# AB_-_Eagle.net
KiCad netlist of a schematic drawn in EAGLE
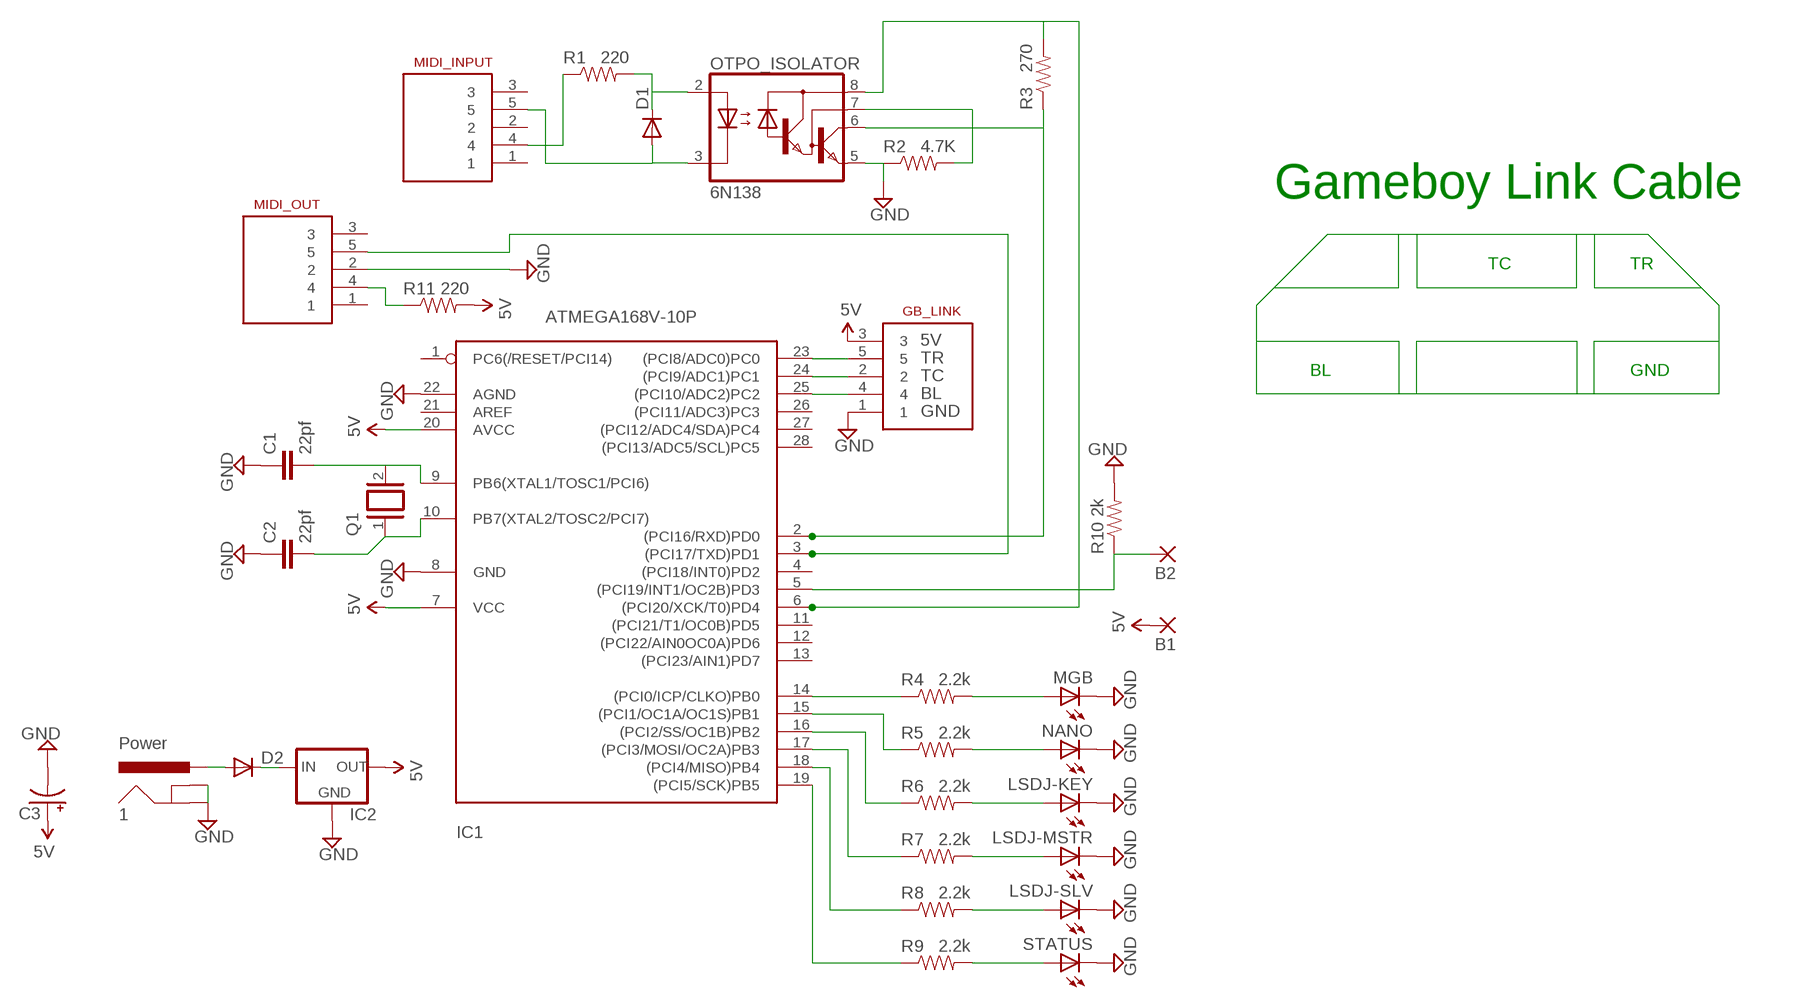
[diagram p0: schematic, sheet 1]

(export (version "E")
  (design (tool "Eeschema 10.0.6"))
  (components
    (comp (ref "1")
      (value "Power")
      (footprint "eagle-import:POWER_JACK_PTH")
      (libsource (lib "eagle-import") (part "POWER_JACKPTH"))
    )
    (comp (ref "B1")
      (value "2,15/1,0")
      (footprint "eagle-import:2,15_1,0")
      (libsource (lib "eagle-import") (part "2,15/1,0"))
    )
    (comp (ref "B2")
      (value "2,15/1,0")
      (footprint "eagle-import:2,15_1,0")
      (libsource (lib "eagle-import") (part "2,15/1,0"))
    )
    (comp (ref "C1")
      (value "22pf")
      (footprint "eagle-import:CAP-PTH-SMALL2")
      (libsource (lib "eagle-import") (part "CAPPTH2"))
    )
    (comp (ref "C2")
      (value "22pf")
      (footprint "eagle-import:CAP-PTH-SMALL2")
      (libsource (lib "eagle-import") (part "CAPPTH2"))
    )
    (comp (ref "C3")
      (value "CAP_POLPTH2")
      (footprint "eagle-import:CPOL-RADIAL-10UF-25V")
      (libsource (lib "eagle-import") (part "CAP_POLPTH2"))
    )
    (comp (ref "D1")
      (value "DIODE1N4148")
      (footprint "eagle-import:DIODE-1N4148")
      (libsource (lib "eagle-import") (part "DIODE1N4148"))
    )
    (comp (ref "D2")
      (value "DIODE1N4148")
      (footprint "eagle-import:DIODE-1N4148")
      (libsource (lib "eagle-import") (part "DIODE1N4148"))
    )
    (comp (ref "GB_LINK")
      (value "MIDI_CONN_FEMALE_SUPPORT")
      (footprint "eagle-import:DIN_5_FEMALE_SUPPORT")
      (libsource (lib "eagle-import") (part "MIDI_CONN_FEMALE_SUPPORT"))
    )
    (comp (ref "IC1")
      (value "ATMEGA168V-10P")
      (footprint "eagle-import:DIL28-3")
      (libsource (lib "eagle-import") (part "ATMEGA168PV-10"))
    )
    (comp (ref "IC2")
      (value "V_REG_78XX-TO-220")
      (footprint "eagle-import:TO-220-ALT")
      (libsource (lib "eagle-import") (part "V_REG_78XX-TO-220"))
    )
    (comp (ref "LSDJ-KEY")
      (value "LED3MM")
      (footprint "eagle-import:LED3MM")
      (libsource (lib "eagle-import") (part "LED3MM"))
    )
    (comp (ref "LSDJ-MSTR")
      (value "LED3MM")
      (footprint "eagle-import:LED3MM")
      (libsource (lib "eagle-import") (part "LED3MM"))
    )
    (comp (ref "LSDJ-SLV")
      (value "LED3MM")
      (footprint "eagle-import:LED3MM")
      (libsource (lib "eagle-import") (part "LED3MM"))
    )
    (comp (ref "MGB")
      (value "LED3MM")
      (footprint "eagle-import:LED3MM")
      (libsource (lib "eagle-import") (part "LED3MM"))
    )
    (comp (ref "MIDI_INPUT")
      (value "MIDI_CONN_FEMALE_SUPPORT")
      (footprint "eagle-import:DIN_5_FEMALE_SUPPORT")
      (libsource (lib "eagle-import") (part "MIDI_CONN_FEMALE_SUPPORT"))
    )
    (comp (ref "MIDI_OUT")
      (value "MIDI_CONN_FEMALE_SUPPORT")
      (footprint "eagle-import:DIN_5_FEMALE_SUPPORT")
      (libsource (lib "eagle-import") (part "MIDI_CONN_FEMALE_SUPPORT"))
    )
    (comp (ref "NANO")
      (value "LED3MM")
      (footprint "eagle-import:LED3MM")
      (libsource (lib "eagle-import") (part "LED3MM"))
    )
    (comp (ref "OTPO_ISOLATOR")
      (value "6N138")
      (footprint "eagle-import:DIL08")
      (fields (field (name "MF") "VISHAY/TELEFUNKEN"))
      (libsource (lib "eagle-import") (part "6N138"))
    )
    (comp (ref "Q1")
      (value "XTAL/S")
      (footprint "eagle-import:QS")
      (libsource (lib "eagle-import") (part "XTAL/S"))
    )
    (comp (ref "R1")
      (value "220")
      (footprint "eagle-import:AXIAL-0.3")
      (libsource (lib "eagle-import") (part "RESISTORAXIAL-0.3"))
    )
    (comp (ref "R2")
      (value "4.7K")
      (footprint "eagle-import:AXIAL-0.3")
      (libsource (lib "eagle-import") (part "RESISTORAXIAL-0.3"))
    )
    (comp (ref "R3")
      (value "270")
      (footprint "eagle-import:AXIAL-0.3")
      (libsource (lib "eagle-import") (part "RESISTORAXIAL-0.3"))
    )
    (comp (ref "R4")
      (value "2.2k")
      (footprint "eagle-import:AXIAL-0.3")
      (libsource (lib "eagle-import") (part "RESISTORAXIAL-0.3"))
    )
    (comp (ref "R5")
      (value "2.2k")
      (footprint "eagle-import:AXIAL-0.3")
      (libsource (lib "eagle-import") (part "RESISTORAXIAL-0.3"))
    )
    (comp (ref "R6")
      (value "2.2k")
      (footprint "eagle-import:AXIAL-0.3")
      (libsource (lib "eagle-import") (part "RESISTORAXIAL-0.3"))
    )
    (comp (ref "R7")
      (value "2.2k")
      (footprint "eagle-import:AXIAL-0.3")
      (libsource (lib "eagle-import") (part "RESISTORAXIAL-0.3"))
    )
    (comp (ref "R8")
      (value "2.2k")
      (footprint "eagle-import:AXIAL-0.3")
      (libsource (lib "eagle-import") (part "RESISTORAXIAL-0.3"))
    )
    (comp (ref "R9")
      (value "2.2k")
      (footprint "eagle-import:AXIAL-0.3")
      (libsource (lib "eagle-import") (part "RESISTORAXIAL-0.3"))
    )
    (comp (ref "R10")
      (value "2k")
      (footprint "eagle-import:AXIAL-0.3")
      (libsource (lib "eagle-import") (part "RESISTORAXIAL-0.3"))
    )
    (comp (ref "R11")
      (value "220")
      (footprint "eagle-import:AXIAL-0.3")
      (libsource (lib "eagle-import") (part "RESISTORAXIAL-0.3"))
    )
    (comp (ref "STATUS")
      (value "LED3MM")
      (footprint "eagle-import:LED3MM")
      (libsource (lib "eagle-import") (part "LED3MM"))
    )
  )
  (nets
    (net (code "1") (name "5V") (class "Default")
      (node (ref "B1") (pin "1") (pinfunction "P_1") (pintype "passive"))
      (node (ref "C3") (pin "1") (pinfunction "+_1") (pintype "passive"))
      (node (ref "GB_LINK") (pin "3") (pinfunction "3_3") (pintype "bidirectional"))
      (node (ref "IC1") (pin "20") (pinfunction "AVCC_20") (pintype "bidirectional"))
      (node (ref "IC1") (pin "7") (pinfunction "VCC_7") (pintype "bidirectional"))
      (node (ref "IC2") (pin "OUT") (pinfunction "OUT_OUT") (pintype "output"))
      (node (ref "R11") (pin "P$2") (pinfunction "2_P$2") (pintype "passive"))
    )
    (net (code "2") (name "GND") (class "Default")
      (node (ref "1") (pin "GND") (pinfunction "GND_GND") (pintype "bidirectional"))
      (node (ref "1") (pin "GNDBREAK") (pinfunction "GNDBREAK_GNDBREAK") (pintype "bidirectional"))
      (node (ref "C1") (pin "1") (pinfunction "1_1") (pintype "passive"))
      (node (ref "C2") (pin "1") (pinfunction "1_1") (pintype "passive"))
      (node (ref "C3") (pin "2") (pinfunction "-_2") (pintype "passive"))
      (node (ref "GB_LINK") (pin "1") (pinfunction "1_1") (pintype "bidirectional"))
      (node (ref "IC1") (pin "22") (pinfunction "AGND_22") (pintype "bidirectional"))
      (node (ref "IC1") (pin "8") (pinfunction "GND_8") (pintype "bidirectional"))
      (node (ref "IC2") (pin "GND") (pinfunction "GND_GND") (pintype "input"))
      (node (ref "LSDJ-KEY") (pin "K") (pinfunction "C_K") (pintype "passive"))
      (node (ref "LSDJ-MSTR") (pin "K") (pinfunction "C_K") (pintype "passive"))
      (node (ref "LSDJ-SLV") (pin "K") (pinfunction "C_K") (pintype "passive"))
      (node (ref "MGB") (pin "K") (pinfunction "C_K") (pintype "passive"))
      (node (ref "MIDI_OUT") (pin "2") (pinfunction "2_2") (pintype "bidirectional"))
      (node (ref "NANO") (pin "K") (pinfunction "C_K") (pintype "passive"))
      (node (ref "OTPO_ISOLATOR") (pin "5") (pinfunction "GND_5") (pintype "passive"))
      (node (ref "R10") (pin "P$2") (pinfunction "2_P$2") (pintype "passive"))
      (node (ref "R2") (pin "P$1") (pinfunction "1_P$1") (pintype "passive"))
      (node (ref "STATUS") (pin "K") (pinfunction "C_K") (pintype "passive"))
    )
    (net (code "3") (name "Net-(1-PadPWR)") (class "Default")
      (node (ref "1") (pin "PWR") (pinfunction "PWR_PWR") (pintype "bidirectional"))
      (node (ref "D2") (pin "A") (pinfunction "A_A") (pintype "passive"))
    )
    (net (code "4") (name "Net-(B2-P)") (class "Default")
      (node (ref "B2") (pin "1") (pinfunction "P_1") (pintype "passive"))
      (node (ref "IC1") (pin "5") (pinfunction "(PCI19/INT1/OC2B)PD3_5") (pintype "bidirectional"))
      (node (ref "R10") (pin "P$1") (pinfunction "1_P$1") (pintype "passive"))
    )
    (net (code "5") (name "Net-(D2-PadC)") (class "Default")
      (node (ref "D2") (pin "C") (pinfunction "C_C") (pintype "passive"))
      (node (ref "IC2") (pin "IN") (pinfunction "IN_IN") (pintype "input"))
    )
    (net (code "6") (name "Net-(IC1-(PCI0{slash}ICP{slash}CLKO)PB0)") (class "Default")
      (node (ref "IC1") (pin "14") (pinfunction "(PCI0/ICP/CLKO)PB0_14") (pintype "bidirectional"))
      (node (ref "R4") (pin "P$1") (pinfunction "1_P$1") (pintype "passive"))
    )
    (net (code "7") (name "Net-(IC1-(PCI1{slash}OC1A{slash}OC1S)PB1)") (class "Default")
      (node (ref "IC1") (pin "15") (pinfunction "(PCI1/OC1A/OC1S)PB1_15") (pintype "bidirectional"))
      (node (ref "R5") (pin "P$1") (pinfunction "1_P$1") (pintype "passive"))
    )
    (net (code "8") (name "Net-(IC1-(PCI2{slash}SS{slash}OC1B)PB2)") (class "Default")
      (node (ref "IC1") (pin "16") (pinfunction "(PCI2/SS/OC1B)PB2_16") (pintype "bidirectional"))
      (node (ref "R6") (pin "P$1") (pinfunction "1_P$1") (pintype "passive"))
    )
    (net (code "9") (name "Net-(IC1-(PCI3{slash}MOSI{slash}OC2A)PB3)") (class "Default")
      (node (ref "IC1") (pin "17") (pinfunction "(PCI3/MOSI/OC2A)PB3_17") (pintype "bidirectional"))
      (node (ref "R7") (pin "P$1") (pinfunction "1_P$1") (pintype "passive"))
    )
    (net (code "10") (name "Net-(IC1-(PCI4{slash}MISO)PB4)") (class "Default")
      (node (ref "IC1") (pin "18") (pinfunction "(PCI4/MISO)PB4_18") (pintype "bidirectional"))
      (node (ref "R8") (pin "P$1") (pinfunction "1_P$1") (pintype "passive"))
    )
    (net (code "11") (name "Net-(IC1-(PCI5{slash}SCK)PB5)") (class "Default")
      (node (ref "IC1") (pin "19") (pinfunction "(PCI5/SCK)PB5_19") (pintype "bidirectional"))
      (node (ref "R9") (pin "P$1") (pinfunction "1_P$1") (pintype "passive"))
    )
    (net (code "12") (name "Net-(IC1-(PCI8{slash}ADC0)PC0)") (class "Default")
      (node (ref "GB_LINK") (pin "5") (pinfunction "5_5") (pintype "bidirectional"))
      (node (ref "IC1") (pin "23") (pinfunction "(PCI8/ADC0)PC0_23") (pintype "bidirectional"))
    )
    (net (code "13") (name "Net-(IC1-(PCI9{slash}ADC1)PC1)") (class "Default")
      (node (ref "GB_LINK") (pin "2") (pinfunction "2_2") (pintype "bidirectional"))
      (node (ref "IC1") (pin "24") (pinfunction "(PCI9/ADC1)PC1_24") (pintype "bidirectional"))
    )
    (net (code "14") (name "Net-(IC1-(PCI10{slash}ADC2)PC2)") (class "Default")
      (node (ref "GB_LINK") (pin "4") (pinfunction "4_4") (pintype "bidirectional"))
      (node (ref "IC1") (pin "25") (pinfunction "(PCI10/ADC2)PC2_25") (pintype "bidirectional"))
    )
    (net (code "15") (name "Net-(IC1-(PCI16{slash}RXD)PD0)") (class "Default")
      (node (ref "IC1") (pin "2") (pinfunction "(PCI16/RXD)PD0_2") (pintype "bidirectional"))
      (node (ref "OTPO_ISOLATOR") (pin "6") (pinfunction "VO_6") (pintype "passive"))
      (node (ref "R3") (pin "P$1") (pinfunction "1_P$1") (pintype "passive"))
    )
    (net (code "16") (name "Net-(IC1-(PCI17{slash}TXD)PD1)") (class "Default")
      (node (ref "IC1") (pin "3") (pinfunction "(PCI17/TXD)PD1_3") (pintype "bidirectional"))
      (node (ref "MIDI_OUT") (pin "5") (pinfunction "5_5") (pintype "bidirectional"))
    )
    (net (code "17") (name "Net-(IC1-(PCI20{slash}XCK{slash}T0)PD4)") (class "Default")
      (node (ref "IC1") (pin "6") (pinfunction "(PCI20/XCK/T0)PD4_6") (pintype "bidirectional"))
      (node (ref "OTPO_ISOLATOR") (pin "8") (pinfunction "VCC_8") (pintype "passive"))
      (node (ref "R3") (pin "P$2") (pinfunction "2_P$2") (pintype "passive"))
    )
    (net (code "18") (name "Net-(IC1-PB6(XTAL1{slash}TOSC1{slash}PCI6))") (class "Default")
      (node (ref "C1") (pin "2") (pinfunction "2_2") (pintype "passive"))
      (node (ref "IC1") (pin "9") (pinfunction "PB6(XTAL1/TOSC1/PCI6)_9") (pintype "bidirectional"))
      (node (ref "Q1") (pin "2") (pinfunction "2_2") (pintype "passive"))
    )
    (net (code "19") (name "Net-(IC1-PB7(XTAL2{slash}TOSC2{slash}PCI7))") (class "Default")
      (node (ref "C2") (pin "2") (pinfunction "2_2") (pintype "passive"))
      (node (ref "IC1") (pin "10") (pinfunction "PB7(XTAL2/TOSC2/PCI7)_10") (pintype "bidirectional"))
      (node (ref "Q1") (pin "1") (pinfunction "1_1") (pintype "passive"))
    )
    (net (code "20") (name "Net-(OTPO_ISOLATOR-A)") (class "Default")
      (node (ref "D1") (pin "C") (pinfunction "C_C") (pintype "passive"))
      (node (ref "OTPO_ISOLATOR") (pin "2") (pinfunction "A_2") (pintype "passive"))
      (node (ref "R1") (pin "P$2") (pinfunction "2_P$2") (pintype "passive"))
    )
    (net (code "21") (name "Net-(OTPO_ISOLATOR-C)") (class "Default")
      (node (ref "D1") (pin "A") (pinfunction "A_A") (pintype "passive"))
      (node (ref "MIDI_INPUT") (pin "5") (pinfunction "5_5") (pintype "bidirectional"))
      (node (ref "OTPO_ISOLATOR") (pin "3") (pinfunction "C_3") (pintype "passive"))
    )
    (net (code "22") (name "Net-(OTPO_ISOLATOR-VB)") (class "Default")
      (node (ref "OTPO_ISOLATOR") (pin "7") (pinfunction "VB_7") (pintype "passive"))
      (node (ref "R2") (pin "P$2") (pinfunction "2_P$2") (pintype "passive"))
    )
    (net (code "23") (name "Net-(R1-1)") (class "Default")
      (node (ref "MIDI_INPUT") (pin "4") (pinfunction "4_4") (pintype "bidirectional"))
      (node (ref "R1") (pin "P$1") (pinfunction "1_P$1") (pintype "passive"))
    )
    (net (code "24") (name "Net-(R4-2)") (class "Default")
      (node (ref "MGB") (pin "A") (pinfunction "A_A") (pintype "passive"))
      (node (ref "R4") (pin "P$2") (pinfunction "2_P$2") (pintype "passive"))
    )
    (net (code "25") (name "Net-(R5-2)") (class "Default")
      (node (ref "NANO") (pin "A") (pinfunction "A_A") (pintype "passive"))
      (node (ref "R5") (pin "P$2") (pinfunction "2_P$2") (pintype "passive"))
    )
    (net (code "26") (name "Net-(R6-2)") (class "Default")
      (node (ref "LSDJ-KEY") (pin "A") (pinfunction "A_A") (pintype "passive"))
      (node (ref "R6") (pin "P$2") (pinfunction "2_P$2") (pintype "passive"))
    )
    (net (code "27") (name "Net-(R7-2)") (class "Default")
      (node (ref "LSDJ-MSTR") (pin "A") (pinfunction "A_A") (pintype "passive"))
      (node (ref "R7") (pin "P$2") (pinfunction "2_P$2") (pintype "passive"))
    )
    (net (code "28") (name "Net-(R8-2)") (class "Default")
      (node (ref "LSDJ-SLV") (pin "A") (pinfunction "A_A") (pintype "passive"))
      (node (ref "R8") (pin "P$2") (pinfunction "2_P$2") (pintype "passive"))
    )
    (net (code "29") (name "Net-(R9-2)") (class "Default")
      (node (ref "R9") (pin "P$2") (pinfunction "2_P$2") (pintype "passive"))
      (node (ref "STATUS") (pin "A") (pinfunction "A_A") (pintype "passive"))
    )
    (net (code "30") (name "Net-(R11-1)") (class "Default")
      (node (ref "MIDI_OUT") (pin "4") (pinfunction "4_4") (pintype "bidirectional"))
      (node (ref "R11") (pin "P$1") (pinfunction "1_P$1") (pintype "passive"))
    )
    (net (code "31") (name "unconnected-(IC1-(PCI11{slash}ADC3)PC3-Pad26)") (class "Default")
      (node (ref "IC1") (pin "26") (pinfunction "(PCI11/ADC3)PC3_26") (pintype "bidirectional"))
    )
    (net (code "32") (name "unconnected-(IC1-(PCI12{slash}ADC4{slash}SDA)PC4-Pad27)") (class "Default")
      (node (ref "IC1") (pin "27") (pinfunction "(PCI12/ADC4/SDA)PC4_27") (pintype "bidirectional"))
    )
    (net (code "33") (name "unconnected-(IC1-(PCI13{slash}ADC5{slash}SCL)PC5-Pad28)") (class "Default")
      (node (ref "IC1") (pin "28") (pinfunction "(PCI13/ADC5/SCL)PC5_28") (pintype "bidirectional"))
    )
    (net (code "34") (name "unconnected-(IC1-(PCI18{slash}INT0)PD2-Pad4)") (class "Default")
      (node (ref "IC1") (pin "4") (pinfunction "(PCI18/INT0)PD2_4") (pintype "bidirectional"))
    )
    (net (code "35") (name "unconnected-(IC1-(PCI21{slash}T1{slash}OC0B)PD5-Pad11)") (class "Default")
      (node (ref "IC1") (pin "11") (pinfunction "(PCI21/T1/OC0B)PD5_11") (pintype "bidirectional"))
    )
    (net (code "36") (name "unconnected-(IC1-(PCI22{slash}AIN0OC0A)PD6-Pad12)") (class "Default")
      (node (ref "IC1") (pin "12") (pinfunction "(PCI22/AIN0OC0A)PD6_12") (pintype "bidirectional"))
    )
    (net (code "37") (name "unconnected-(IC1-(PCI23{slash}AIN1)PD7-Pad13)") (class "Default")
      (node (ref "IC1") (pin "13") (pinfunction "(PCI23/AIN1)PD7_13") (pintype "bidirectional"))
    )
    (net (code "38") (name "unconnected-(IC1-AREF-Pad21)") (class "Default")
      (node (ref "IC1") (pin "21") (pinfunction "AREF_21") (pintype "bidirectional"))
    )
    (net (code "39") (name "unconnected-(IC1-PC6({slash}RESET{slash}PCI14)-Pad1)") (class "Default")
      (node (ref "IC1") (pin "1") (pinfunction "PC6(/RESET/PCI14)_1") (pintype "bidirectional"))
    )
    (net (code "40") (name "unconnected-(MIDI_INPUT-Pad1)") (class "Default")
      (node (ref "MIDI_INPUT") (pin "1") (pinfunction "1_1") (pintype "bidirectional"))
    )
    (net (code "41") (name "unconnected-(MIDI_INPUT-Pad2)") (class "Default")
      (node (ref "MIDI_INPUT") (pin "2") (pinfunction "2_2") (pintype "bidirectional"))
    )
    (net (code "42") (name "unconnected-(MIDI_INPUT-Pad3)") (class "Default")
      (node (ref "MIDI_INPUT") (pin "3") (pinfunction "3_3") (pintype "bidirectional"))
    )
    (net (code "43") (name "unconnected-(MIDI_OUT-Pad1)") (class "Default")
      (node (ref "MIDI_OUT") (pin "1") (pinfunction "1_1") (pintype "bidirectional"))
    )
    (net (code "44") (name "unconnected-(MIDI_OUT-Pad3)") (class "Default")
      (node (ref "MIDI_OUT") (pin "3") (pinfunction "3_3") (pintype "bidirectional"))
    )
  )
)
